# Arduino_I2C.net
KiCad netlist of a schematic drawn in EAGLE
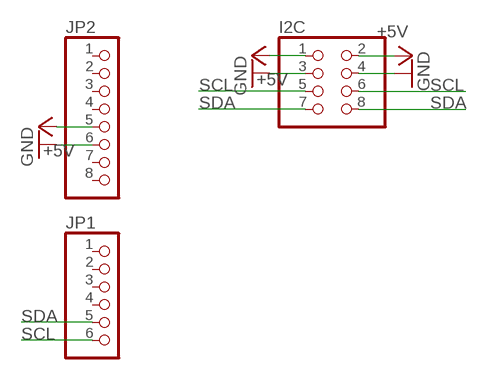
[diagram p0: schematic, sheet 1]

(export (version "E")
  (design (tool "Eeschema 10.0.6"))
  (components
    (comp (ref "I2C")
      (value "PINHD-2X4")
      (footprint "eagle-import:2X04")
      (libsource (lib "eagle-import") (part "PINHD-2X4"))
    )
    (comp (ref "JP1")
      (value "PINHD-1X6CLEAN")
      (footprint "eagle-import:1X06-CLEAN")
      (libsource (lib "eagle-import") (part "PINHD-1X6CLEAN"))
    )
    (comp (ref "JP2")
      (value "PINHD-1X8CLEANBIG")
      (footprint "eagle-import:1X08-CLEANBIG")
      (libsource (lib "eagle-import") (part "PINHD-1X8CLEANBIG"))
    )
  )
  (nets
    (net (code "1") (name "+5V") (class "Default")
      (node (ref "I2C") (pin "1") (pinfunction "1_1") (pintype "passive"))
      (node (ref "I2C") (pin "2") (pinfunction "2_2") (pintype "passive"))
      (node (ref "JP2") (pin "5") (pinfunction "5_5") (pintype "passive"))
    )
    (net (code "2") (name "/SCL") (class "Default")
      (node (ref "I2C") (pin "5") (pinfunction "5_5") (pintype "passive"))
      (node (ref "I2C") (pin "6") (pinfunction "6_6") (pintype "passive"))
      (node (ref "JP1") (pin "6") (pinfunction "6_6") (pintype "passive"))
    )
    (net (code "3") (name "/SDA") (class "Default")
      (node (ref "I2C") (pin "7") (pinfunction "7_7") (pintype "passive"))
      (node (ref "I2C") (pin "8") (pinfunction "8_8") (pintype "passive"))
      (node (ref "JP1") (pin "5") (pinfunction "5_5") (pintype "passive"))
    )
    (net (code "4") (name "GND") (class "Default")
      (node (ref "I2C") (pin "3") (pinfunction "3_3") (pintype "passive"))
      (node (ref "I2C") (pin "4") (pinfunction "4_4") (pintype "passive"))
      (node (ref "JP2") (pin "6") (pinfunction "6_6") (pintype "passive"))
    )
    (net (code "5") (name "unconnected-(JP1-Pad1)") (class "Default")
      (node (ref "JP1") (pin "1") (pinfunction "1_1") (pintype "passive"))
    )
    (net (code "6") (name "unconnected-(JP1-Pad2)") (class "Default")
      (node (ref "JP1") (pin "2") (pinfunction "2_2") (pintype "passive"))
    )
    (net (code "7") (name "unconnected-(JP1-Pad3)") (class "Default")
      (node (ref "JP1") (pin "3") (pinfunction "3_3") (pintype "passive"))
    )
    (net (code "8") (name "unconnected-(JP1-Pad4)") (class "Default")
      (node (ref "JP1") (pin "4") (pinfunction "4_4") (pintype "passive"))
    )
    (net (code "9") (name "unconnected-(JP2-Pad1)") (class "Default")
      (node (ref "JP2") (pin "1") (pinfunction "1_1") (pintype "passive"))
    )
    (net (code "10") (name "unconnected-(JP2-Pad2)") (class "Default")
      (node (ref "JP2") (pin "2") (pinfunction "2_2") (pintype "passive"))
    )
    (net (code "11") (name "unconnected-(JP2-Pad3)") (class "Default")
      (node (ref "JP2") (pin "3") (pinfunction "3_3") (pintype "passive"))
    )
    (net (code "12") (name "unconnected-(JP2-Pad4)") (class "Default")
      (node (ref "JP2") (pin "4") (pinfunction "4_4") (pintype "passive"))
    )
    (net (code "13") (name "unconnected-(JP2-Pad7)") (class "Default")
      (node (ref "JP2") (pin "7") (pinfunction "7_7") (pintype "passive"))
    )
    (net (code "14") (name "unconnected-(JP2-Pad8)") (class "Default")
      (node (ref "JP2") (pin "8") (pinfunction "8_8") (pintype "passive"))
    )
  )
)
